# Hochsetzsteller.net
KiCad netlist of a schematic drawn in Altium Designer
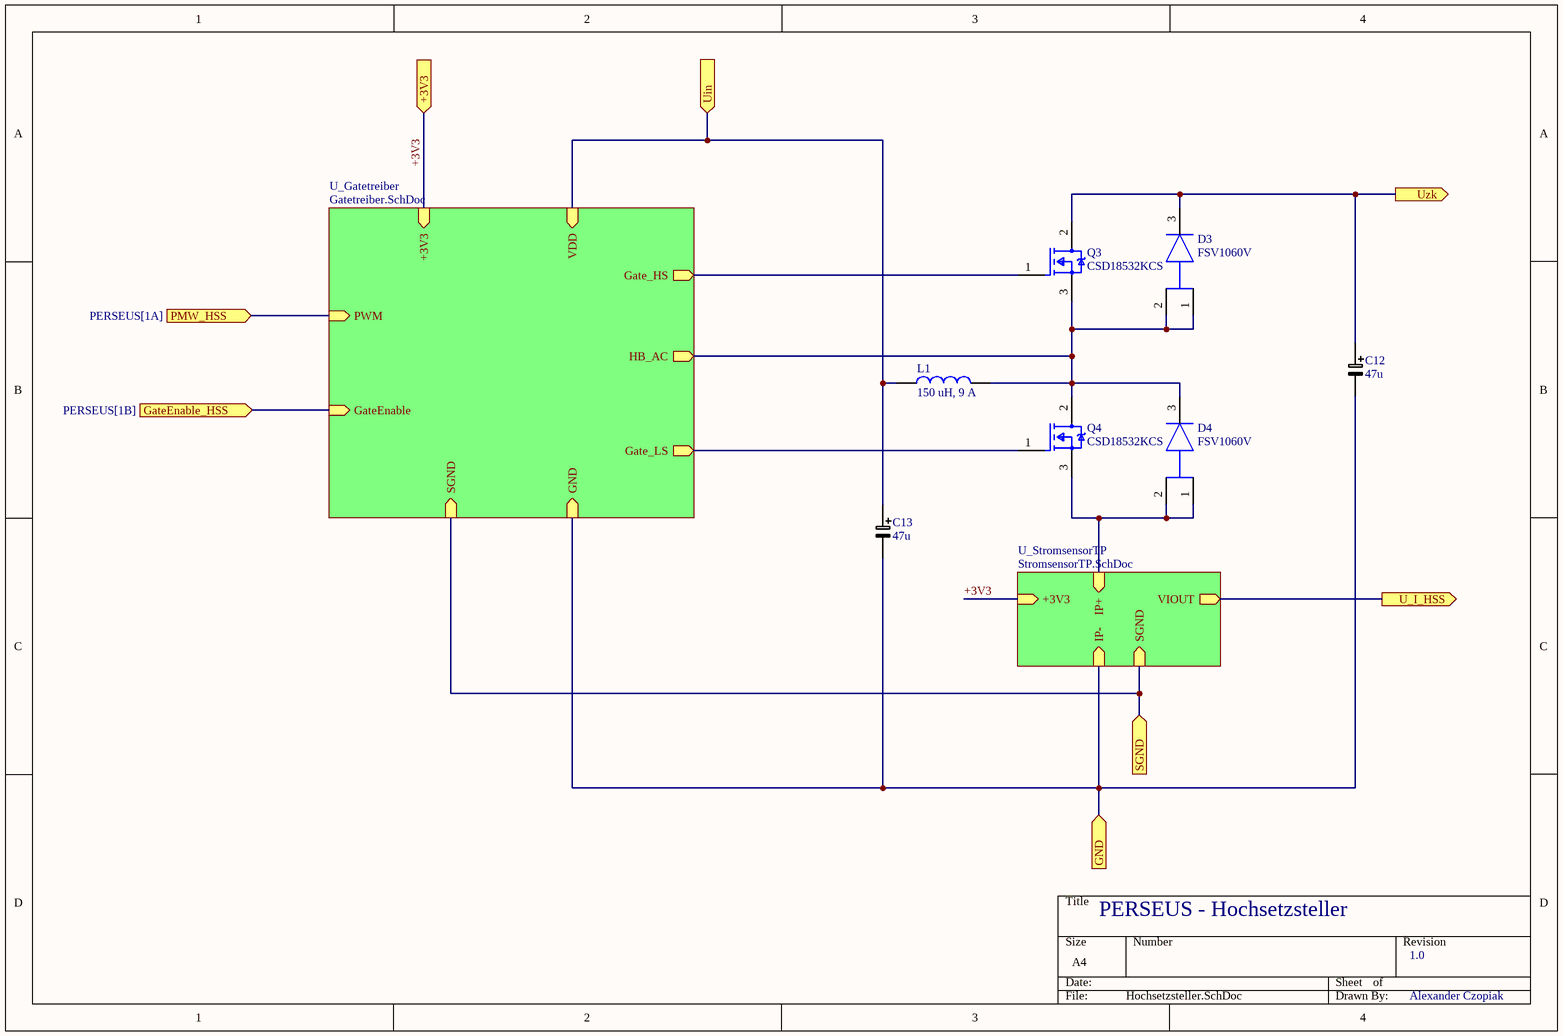
[diagram p0: Hochsetzsteller.SchDoc]

(export (version "E")
  (design (tool "Eeschema 10.0.6"))
  (components
    (comp (ref "C12")
      (value "47u")
      (footprint "ELKO_5MM_D12.5MM")
      (description "Kondensator Elektrolyt")
      (libsource (lib "HSLS_Parts") (part "ELKO_THT"))
    )
    (comp (ref "C13")
      (value "47u")
      (footprint "ELKO_5MM_D12.5MM")
      (description "Kondensator Elektrolyt")
      (libsource (lib "HSLS_Parts") (part "ELKO_THT"))
    )
    (comp (ref "D3")
      (value "FSV1060V")
      (footprint "FP-340BQ-MFG")
      (description "DIODE SCHOTTKY 60V 10A TO277-3")
      (fields
        (field (name "MANUFACTURER") "ON Semiconductor")
        (field (name "OCTOPART") "https://octopart.com/fsv1060v-on+semiconductor-84328651")
      )
      (libsource (lib "Altium Content Vault") (part "4936ed7bdd82a3c6bbc3cb868a43564"))
    )
    (comp (ref "D4")
      (value "FSV1060V")
      (footprint "FP-340BQ-MFG")
      (description "DIODE SCHOTTKY 60V 10A TO277-3")
      (fields
        (field (name "MANUFACTURER") "ON Semiconductor")
        (field (name "OCTOPART") "https://octopart.com/fsv1060v-on+semiconductor-84328651")
      )
      (libsource (lib "Altium Content Vault") (part "4936ed7bdd82a3c6bbc3cb868a43564"))
    )
    (comp (ref "L1")
      (value "150 uH, 9 A")
      (footprint "WE-HCF_2920_Litz")
      (description "SMT High Current Inductor WE-HCF, size 2920, 150 uH, 8.4 A")
      (fields (field (name "PART NUMBER") "74437429203151") (field (name "PUBLISHER") "Wurth Elektronik"))
      (libsource (lib "HSLS_Parts") (part "Induktivitaet SMD"))
    )
    (comp (ref "Q3")
      (value "CSD18532KCS")
      (footprint "FP-PG-TO220-3-MFG")
      (description "MOSFET N-CH 60V 100A TO220")
      (libsource (lib "Altium Content Vault") (part "8b62d417cbef8344eebe0bde0c45977"))
    )
    (comp (ref "Q4")
      (value "CSD18532KCS")
      (footprint "FP-PG-TO220-3-MFG")
      (description "MOSFET N-CH 60V 100A TO220")
      (libsource (lib "Altium Content Vault") (part "8b62d417cbef8344eebe0bde0c45977"))
    )
  )
  (nets
    (net (code "2") (name "/GND") (class "Default")
      (node (ref "C12") (pin "2") (pinfunction "2_2") (pintype "passive"))
      (node (ref "C13") (pin "2") (pinfunction "2_2") (pintype "passive"))
    )
    (net (code "4") (name "/Gate_HS") (class "Default")
      (node (ref "Q3") (pin "1") (pinfunction "GATE_1") (pintype "passive"))
    )
    (net (code "5") (name "/Gate_LS") (class "Default")
      (node (ref "Q4") (pin "1") (pinfunction "GATE_1") (pintype "passive"))
    )
    (net (code "6") (name "/HB_AC") (class "Default")
      (node (ref "D3") (pin "1") (pinfunction "Anode_1_1") (pintype "passive"))
      (node (ref "D3") (pin "2") (pinfunction "Anode_2_2") (pintype "passive"))
      (node (ref "D4") (pin "3") (pinfunction "C_3") (pintype "passive"))
      (node (ref "L1") (pin "2") (pinfunction "2_2") (pintype "passive"))
      (node (ref "Q3") (pin "3") (pinfunction "SOURCE_3") (pintype "passive"))
      (node (ref "Q4") (pin "2") (pinfunction "DRAIN_2") (pintype "passive"))
    )
    (net (code "7") (name "/IP+") (class "Default")
      (node (ref "D4") (pin "1") (pinfunction "Anode_1_1") (pintype "passive"))
      (node (ref "D4") (pin "2") (pinfunction "Anode_2_2") (pintype "passive"))
      (node (ref "Q4") (pin "3") (pinfunction "SOURCE_3") (pintype "passive"))
    )
    (net (code "11") (name "/Uin") (class "Default")
      (node (ref "C13") (pin "1") (pinfunction "1_1") (pintype "passive"))
      (node (ref "L1") (pin "1") (pinfunction "1_1") (pintype "passive"))
    )
    (net (code "12") (name "/Uzk") (class "Default")
      (node (ref "C12") (pin "1") (pinfunction "1_1") (pintype "passive"))
      (node (ref "D3") (pin "3") (pinfunction "C_3") (pintype "passive"))
      (node (ref "Q3") (pin "2") (pinfunction "DRAIN_2") (pintype "passive"))
    )
  )
)
